# RF.net
KiCad netlist of a schematic drawn in Altium Designer
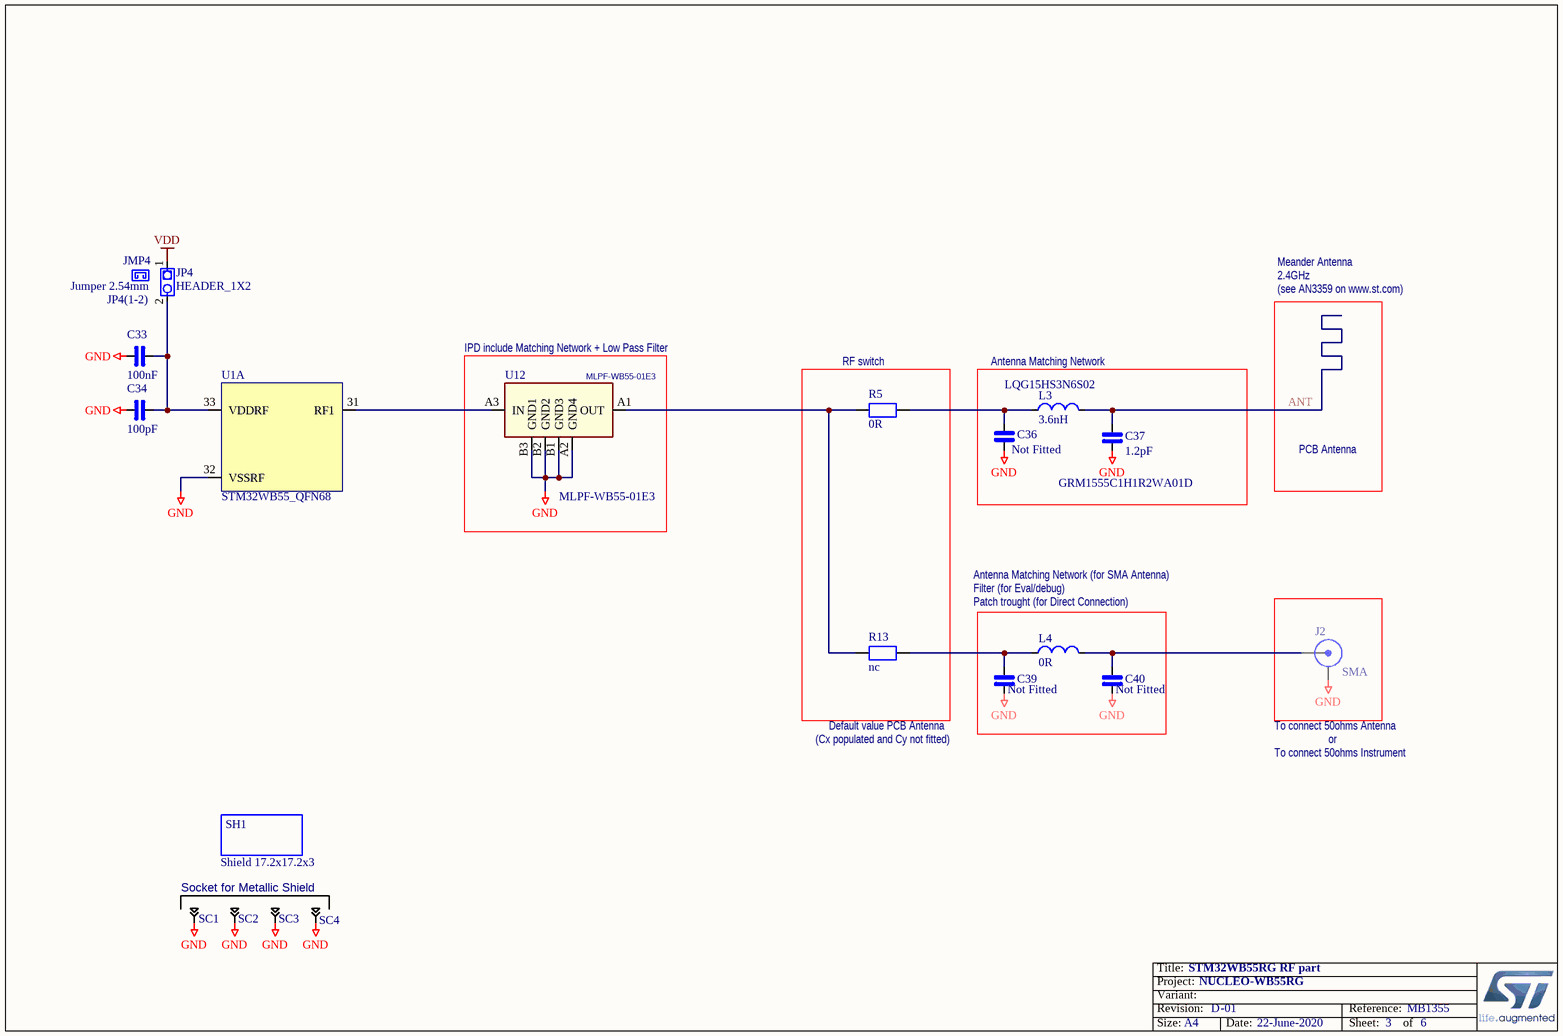
[diagram p0: RF.SchDoc]

(export (version "E")
  (design (tool "Eeschema 10.0.6"))
  (components
    (comp (ref "C33")
      (value "100nF")
      (footprint "0402_CAP_NPOL")
      (description "Capacitor_not polarized")
      (libsource (lib "ST_Lib3D") (part "CAP_NPOL"))
    )
    (comp (ref "C34")
      (value "100pF")
      (footprint "0402_CAP_NPOL")
      (description "Capacitor_not polarized")
      (libsource (lib "ST_Lib3D") (part "CAP_NPOL"))
    )
    (comp (ref "C36")
      (value "~")
      (footprint "0402_CAP_NPOL")
      (description "Capacitor_not polarized")
      (fields (field (name "FITTED") "Not Fitted"))
      (libsource (lib "ST_Lib3D") (part "CAP_NPOL"))
    )
    (comp (ref "C37")
      (value "1.2pF")
      (footprint "0402_CAP_NPOL")
      (description "Capacitor_not polarized")
      (fields (field (name "REF") "GRM1555C1H1R2WA01D"))
      (libsource (lib "ST_Lib3D") (part "CAP_NPOL"))
    )
    (comp (ref "C39")
      (value "~")
      (footprint "0402_CAP_NPOL")
      (description "Capacitor_not polarized")
      (fields (field (name "FITTED") "Not Fitted"))
      (libsource (lib "ST_Lib3D") (part "CAP_NPOL"))
    )
    (comp (ref "C40")
      (value "~")
      (footprint "0402_CAP_NPOL")
      (description "Capacitor_not polarized")
      (fields (field (name "FITTED") "Not Fitted"))
      (libsource (lib "ST_Lib3D") (part "CAP_NPOL"))
    )
    (comp (ref "J2") (value "SMA") (footprint "SMA_T_9.52_NF") (libsource (lib "RF connector") (part "SMA")))
    (comp (ref "JMP4")
      (value "Jumper 2.54mm")
      (footprint "Jumper 2.54mm BLACK")
      (fields (field (name "DEFAULT") "JP4(1-2)"))
      (libsource (lib "Connector") (part "Jumper 2.54mm"))
    )
    (comp (ref "JP4")
      (value "HEADER_1X2")
      (footprint "Header M 1x2x2.54 TH V")
      (libsource (lib "Connector") (part "HEADER_1X2_L"))
    )
    (comp (ref "L3")
      (value "3.6nH")
      (footprint "0402_COIL")
      (fields (field (name "REF") "LQG15HS3N6S02"))
      (libsource (lib "Passive") (part "INDUCTOR_SMD_STDL"))
    )
    (comp (ref "L4")
      (value "0R")
      (footprint "0402_COIL")
      (libsource (lib "Passive") (part "INDUCTOR_SMD_STDL"))
    )
    (comp (ref "R5")
      (value "0R")
      (footprint "0402_RES")
      (description "Resistor")
      (libsource (lib "Lib3D_Altium10_Schlib") (part "RES"))
    )
    (comp (ref "R13")
      (value "nc")
      (footprint "0402_RES")
      (description "Resistor")
      (libsource (lib "Lib3D_Altium10_Schlib") (part "RES"))
    )
    (comp (ref "SC1")
      (value "Shield Clip_A 3.9x1.1x1.28")
      (footprint "Shield Clip_A 3.9x1.1x1.28")
      (description "Harwin S0951-46R")
      (libsource (lib "Box_Meca") (part "Shield Clip_A 3.9x1.1x1.28"))
    )
    (comp (ref "SC2")
      (value "Shield Clip_A 3.9x1.1x1.28")
      (footprint "Shield Clip_A 3.9x1.1x1.28")
      (description "Harwin S0951-46R")
      (libsource (lib "Box_Meca") (part "Shield Clip_A 3.9x1.1x1.28"))
    )
    (comp (ref "SC3")
      (value "Shield Clip_A 3.9x1.1x1.28")
      (footprint "Shield Clip_A 3.9x1.1x1.28")
      (description "Harwin S0951-46R")
      (libsource (lib "Box_Meca") (part "Shield Clip_A 3.9x1.1x1.28"))
    )
    (comp (ref "SC4")
      (value "Shield Clip_A 3.9x1.1x1.28")
      (footprint "Shield Clip_A 3.9x1.1x1.28")
      (description "Harwin S0951-46R")
      (libsource (lib "Box_Meca") (part "Shield Clip_A 3.9x1.1x1.28"))
    )
    (comp (ref "SH1")
      (value "Shield 17.2x17.2x3")
      (footprint "Shield 17.2x17.2x3")
      (description "Shield")
      (libsource (lib "Box_Meca") (part "Shield"))
    )
    (comp (ref "U1")
      (value "STM32WB55_QFN68")
      (footprint "VFQFPN68_8x8x0.1_p0.4")
      (libsource (lib "Active") (part "STM32WBxx_QFN68"))
    )
    (comp (ref "U12")
      (value "MLPF-WB55-01E3")
      (footprint "ST_CSP650x58P2x3_160x100x42")
      (description "2.4 GHz low pass filter matched to STM32WBx5Cx/Rx")
      (fields
        (field (name "INTERNAL_PART_NUMBER") "MCD-02059")
        (field (name "ALTIUM_VALUE") "MLPF-WB55-01E3")
        (field (name "MANUFACTURER") "STMICROELECTRONICS")
        (field (name "PROVIDED_BY") "SUBCO with ST control")
      )
      (libsource (lib "MCD_PARTS_database") (part "MLPF-WB55-01E3"))
    )
  )
  (nets
    (net (code "1") (name "/ANT") (class "Default")
      (node (ref "C37") (pin "2") (pinfunction "2_2") (pintype "passive"))
      (node (ref "L3") (pin "2") (pinfunction "2_2") (pintype "passive"))
    )
    (net (code "2") (name "GND") (class "Default")
      (node (ref "C33") (pin "1") (pinfunction "1_1") (pintype "passive"))
      (node (ref "C34") (pin "1") (pinfunction "1_1") (pintype "passive"))
      (node (ref "C36") (pin "2") (pinfunction "2_2") (pintype "passive"))
      (node (ref "C37") (pin "1") (pinfunction "1_1") (pintype "passive"))
      (node (ref "C39") (pin "1") (pinfunction "1_1") (pintype "passive"))
      (node (ref "C40") (pin "1") (pinfunction "1_1") (pintype "passive"))
      (node (ref "J2") (pin "2") (pinfunction "Y_2") (pintype "passive"))
      (node (ref "SC1") (pin "1") (pinfunction "1_1") (pintype "passive"))
      (node (ref "SC2") (pin "1") (pinfunction "1_1") (pintype "passive"))
      (node (ref "SC3") (pin "1") (pinfunction "1_1") (pintype "passive"))
      (node (ref "SC4") (pin "1") (pinfunction "1_1") (pintype "passive"))
      (node (ref "U1") (pin "32") (pinfunction "VSSRF_32") (pintype "passive"))
      (node (ref "U12") (pin "A2") (pinfunction "GND4_A2") (pintype "passive"))
      (node (ref "U12") (pin "B1") (pinfunction "GND3_B1") (pintype "passive"))
      (node (ref "U12") (pin "B2") (pinfunction "GND2_B2") (pintype "passive"))
      (node (ref "U12") (pin "B3") (pinfunction "GND1_B3") (pintype "passive"))
    )
    (net (code "3") (name "Net-(C36-Pad1)") (class "Default")
      (node (ref "C36") (pin "1") (pinfunction "1_1") (pintype "passive"))
      (node (ref "L3") (pin "1") (pinfunction "1_1") (pintype "passive"))
      (node (ref "R5") (pin "2") (pinfunction "2_2") (pintype "passive"))
    )
    (net (code "4") (name "Net-(C39-Pad2)") (class "Default")
      (node (ref "C39") (pin "2") (pinfunction "2_2") (pintype "passive"))
      (node (ref "L4") (pin "1") (pinfunction "1_1") (pintype "passive"))
      (node (ref "R13") (pin "2") (pinfunction "2_2") (pintype "passive"))
    )
    (net (code "5") (name "Net-(J2-X)") (class "Default")
      (node (ref "C40") (pin "2") (pinfunction "2_2") (pintype "passive"))
      (node (ref "J2") (pin "1") (pinfunction "X_1") (pintype "passive"))
      (node (ref "L4") (pin "2") (pinfunction "2_2") (pintype "passive"))
    )
    (net (code "6") (name "Net-(U1A-VDDRF)") (class "Default")
      (node (ref "C33") (pin "2") (pinfunction "2_2") (pintype "passive"))
      (node (ref "C34") (pin "2") (pinfunction "2_2") (pintype "passive"))
      (node (ref "JP4") (pin "2") (pinfunction "2_2") (pintype "passive"))
      (node (ref "U1") (pin "33") (pinfunction "VDDRF_33") (pintype "passive"))
    )
    (net (code "7") (name "Net-(U12-IN)") (class "Default")
      (node (ref "U1") (pin "31") (pinfunction "RF1_31") (pintype "passive"))
      (node (ref "U12") (pin "A3") (pinfunction "IN_A3") (pintype "passive"))
    )
    (net (code "8") (name "Net-(U12-OUT)") (class "Default")
      (node (ref "R13") (pin "1") (pinfunction "1_1") (pintype "passive"))
      (node (ref "R5") (pin "1") (pinfunction "1_1") (pintype "passive"))
      (node (ref "U12") (pin "A1") (pinfunction "OUT_A1") (pintype "passive"))
    )
    (net (code "9") (name "VDD") (class "Default")
      (node (ref "JP4") (pin "1") (pinfunction "1_1") (pintype "passive"))
    )
  )
)
